# version3.net
KiCad netlist of a schematic drawn in EAGLE
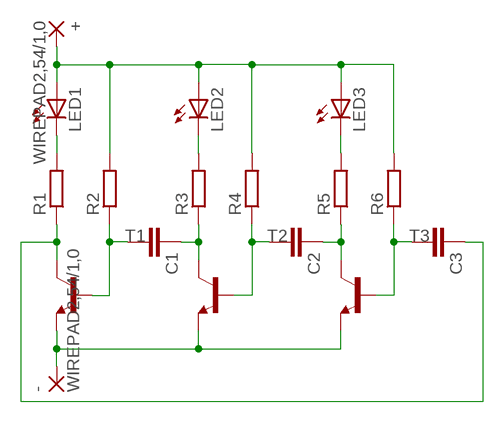
[diagram p0: schematic, sheet 1]

(export (version "E")
  (design (tool "Eeschema 10.0.6"))
  (components
    (comp (ref "+")
      (value "WIREPAD2,54/1,0")
      (footprint "eagle-import:2,54_1,0")
      (libsource (lib "eagle-import") (part "WIREPAD2,54/1,0"))
    )
    (comp (ref "-")
      (value "WIREPAD2,54/1,0")
      (footprint "eagle-import:2,54_1,0")
      (libsource (lib "eagle-import") (part "WIREPAD2,54/1,0"))
    )
    (comp (ref "C1")
      (value "C-EUC0603")
      (footprint "eagle-import:C0603")
      (libsource (lib "eagle-import") (part "C-EUC0603"))
    )
    (comp (ref "C2")
      (value "C-EUC0603")
      (footprint "eagle-import:C0603")
      (libsource (lib "eagle-import") (part "C-EUC0603"))
    )
    (comp (ref "C3")
      (value "C-EUC0603")
      (footprint "eagle-import:C0603")
      (libsource (lib "eagle-import") (part "C-EUC0603"))
    )
    (comp (ref "LED1")
      (value "LEDSML0603")
      (footprint "eagle-import:SML0603")
      (libsource (lib "eagle-import") (part "LEDSML0603"))
    )
    (comp (ref "LED2")
      (value "LEDSML0603")
      (footprint "eagle-import:SML0603")
      (libsource (lib "eagle-import") (part "LEDSML0603"))
    )
    (comp (ref "LED3")
      (value "LEDSML0603")
      (footprint "eagle-import:SML0603")
      (libsource (lib "eagle-import") (part "LEDSML0603"))
    )
    (comp (ref "R1")
      (value "R-EU_R0603")
      (footprint "eagle-import:R0603")
      (libsource (lib "eagle-import") (part "R-EU_R0603"))
    )
    (comp (ref "R2")
      (value "R-EU_R0603")
      (footprint "eagle-import:R0603")
      (libsource (lib "eagle-import") (part "R-EU_R0603"))
    )
    (comp (ref "R3")
      (value "R-EU_R0603")
      (footprint "eagle-import:R0603")
      (libsource (lib "eagle-import") (part "R-EU_R0603"))
    )
    (comp (ref "R4")
      (value "R-EU_R0603")
      (footprint "eagle-import:R0603")
      (libsource (lib "eagle-import") (part "R-EU_R0603"))
    )
    (comp (ref "R5")
      (value "R-EU_R0603")
      (footprint "eagle-import:R0603")
      (libsource (lib "eagle-import") (part "R-EU_R0603"))
    )
    (comp (ref "R6")
      (value "R-EU_R0603")
      (footprint "eagle-import:R0603")
      (libsource (lib "eagle-import") (part "R-EU_R0603"))
    )
    (comp (ref "T1")
      (value "MMBT2222ALT1-NPN-SOT23-BEC")
      (footprint "eagle-import:SOT23-BEC")
      (libsource (lib "eagle-import") (part "-NPN-SOT23-BECMMBT2222ALT1"))
    )
    (comp (ref "T2")
      (value "MMBT2222ALT1-NPN-SOT23-BEC")
      (footprint "eagle-import:SOT23-BEC")
      (libsource (lib "eagle-import") (part "-NPN-SOT23-BECMMBT2222ALT1"))
    )
    (comp (ref "T3")
      (value "MMBT2222ALT1-NPN-SOT23-BEC")
      (footprint "eagle-import:SOT23-BEC")
      (libsource (lib "eagle-import") (part "-NPN-SOT23-BECMMBT2222ALT1"))
    )
  )
  (nets
    (net (code "1") (name "Net-(+-P)") (class "Default")
      (node (ref "+") (pin "1") (pinfunction "P_1") (pintype "passive"))
      (node (ref "LED1") (pin "A") (pinfunction "A_A") (pintype "passive"))
      (node (ref "LED2") (pin "A") (pinfunction "A_A") (pintype "passive"))
      (node (ref "LED3") (pin "A") (pinfunction "A_A") (pintype "passive"))
      (node (ref "R2") (pin "2") (pinfunction "2_2") (pintype "passive"))
      (node (ref "R4") (pin "2") (pinfunction "2_2") (pintype "passive"))
      (node (ref "R6") (pin "2") (pinfunction "2_2") (pintype "passive"))
    )
    (net (code "2") (name "Net-(--P)") (class "Default")
      (node (ref "-") (pin "1") (pinfunction "P_1") (pintype "passive"))
      (node (ref "T1") (pin "E") (pinfunction "E_E") (pintype "passive"))
      (node (ref "T2") (pin "E") (pinfunction "E_E") (pintype "passive"))
      (node (ref "T3") (pin "E") (pinfunction "E_E") (pintype "passive"))
    )
    (net (code "3") (name "Net-(C1-Pad1)") (class "Default")
      (node (ref "C1") (pin "1") (pinfunction "1_1") (pintype "passive"))
      (node (ref "R3") (pin "1") (pinfunction "1_1") (pintype "passive"))
      (node (ref "T2") (pin "C") (pinfunction "C_C") (pintype "passive"))
    )
    (net (code "4") (name "Net-(C1-Pad2)") (class "Default")
      (node (ref "C1") (pin "2") (pinfunction "2_2") (pintype "passive"))
      (node (ref "R2") (pin "1") (pinfunction "1_1") (pintype "passive"))
      (node (ref "T1") (pin "B") (pinfunction "B_B") (pintype "passive"))
    )
    (net (code "5") (name "Net-(C2-Pad1)") (class "Default")
      (node (ref "C2") (pin "1") (pinfunction "1_1") (pintype "passive"))
      (node (ref "R5") (pin "1") (pinfunction "1_1") (pintype "passive"))
      (node (ref "T3") (pin "C") (pinfunction "C_C") (pintype "passive"))
    )
    (net (code "6") (name "Net-(C2-Pad2)") (class "Default")
      (node (ref "C2") (pin "2") (pinfunction "2_2") (pintype "passive"))
      (node (ref "R4") (pin "1") (pinfunction "1_1") (pintype "passive"))
      (node (ref "T2") (pin "B") (pinfunction "B_B") (pintype "passive"))
    )
    (net (code "7") (name "Net-(C3-Pad1)") (class "Default")
      (node (ref "C3") (pin "1") (pinfunction "1_1") (pintype "passive"))
      (node (ref "R1") (pin "1") (pinfunction "1_1") (pintype "passive"))
      (node (ref "T1") (pin "C") (pinfunction "C_C") (pintype "passive"))
    )
    (net (code "8") (name "Net-(C3-Pad2)") (class "Default")
      (node (ref "C3") (pin "2") (pinfunction "2_2") (pintype "passive"))
      (node (ref "R6") (pin "1") (pinfunction "1_1") (pintype "passive"))
      (node (ref "T3") (pin "B") (pinfunction "B_B") (pintype "passive"))
    )
    (net (code "9") (name "Net-(LED1-PadC)") (class "Default")
      (node (ref "LED1") (pin "C") (pinfunction "C_C") (pintype "passive"))
      (node (ref "R1") (pin "2") (pinfunction "2_2") (pintype "passive"))
    )
    (net (code "10") (name "Net-(LED2-PadC)") (class "Default")
      (node (ref "LED2") (pin "C") (pinfunction "C_C") (pintype "passive"))
      (node (ref "R3") (pin "2") (pinfunction "2_2") (pintype "passive"))
    )
    (net (code "11") (name "Net-(LED3-PadC)") (class "Default")
      (node (ref "LED3") (pin "C") (pinfunction "C_C") (pintype "passive"))
      (node (ref "R5") (pin "2") (pinfunction "2_2") (pintype "passive"))
    )
  )
)
